# SCH_SIM808_ArduinoNano.net
KiCad netlist of a schematic drawn in Altium Designer
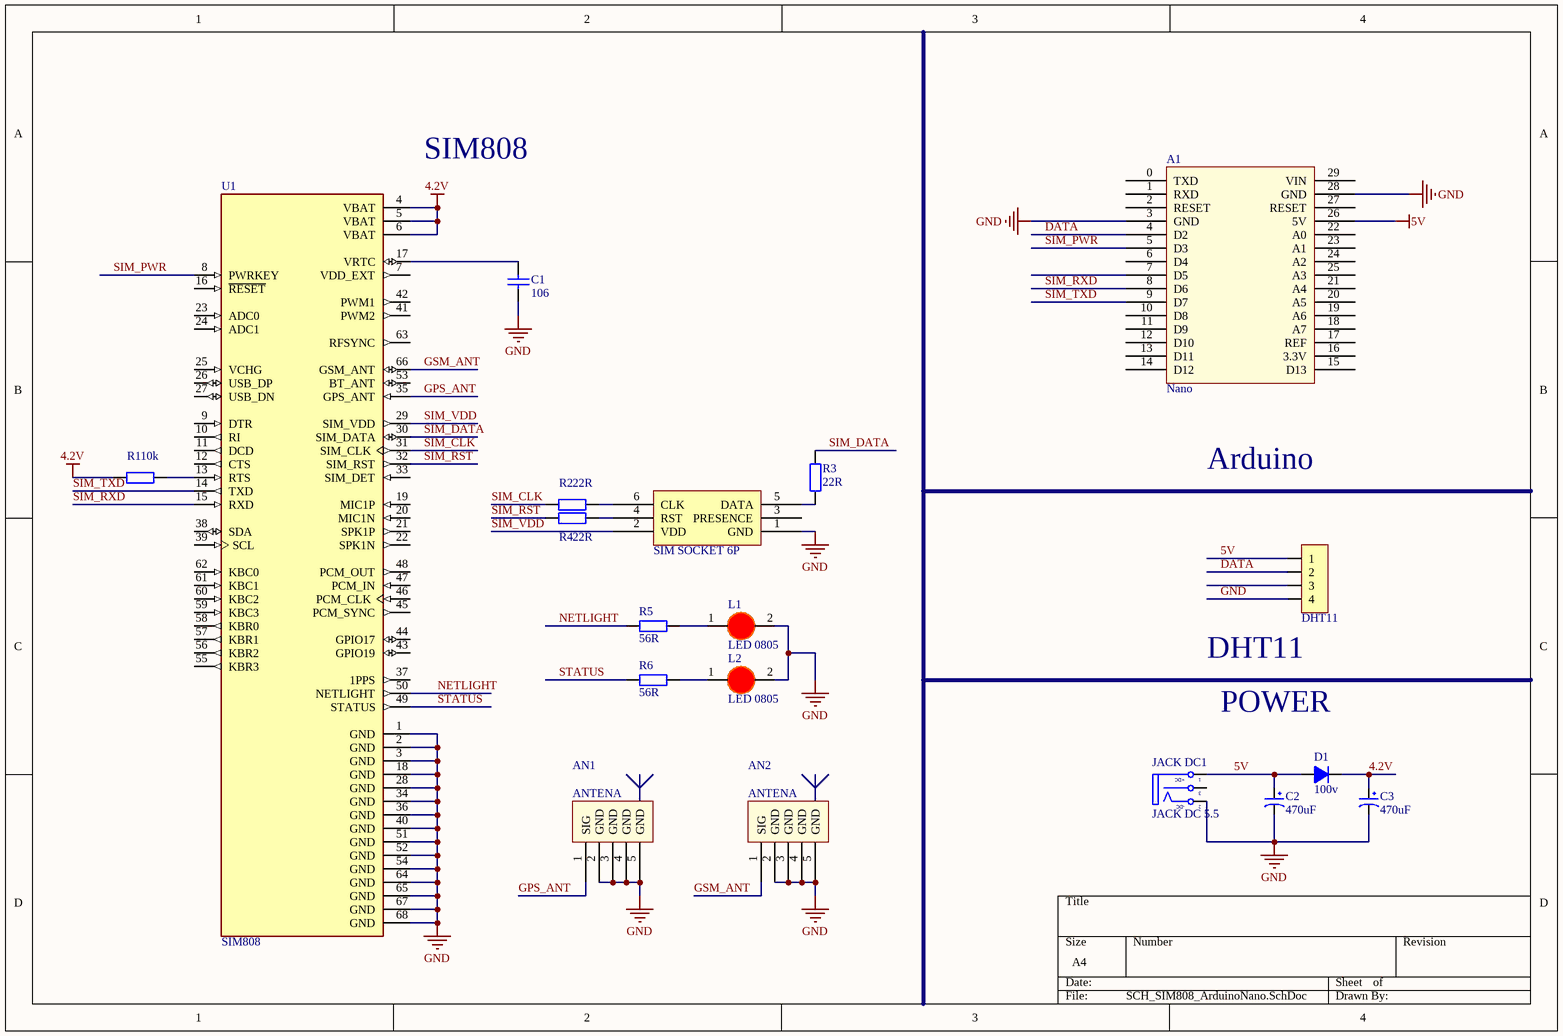
[diagram p0: SCH_SIM808_ArduinoNano.SchDoc]

(export (version "E")
  (design (tool "Eeschema 10.0.6"))
  (components
    (comp (ref "A1")
      (value "Nano")
      (footprint "Arduino nano")
      (libsource (lib "Altium_Lib_by_KhueNguyenCreator") (part "Arduino Nano"))
    )
    (comp (ref "AN1")
      (value "ANTENA")
      (footprint "DE ANTEN SMA CONG")
      (description "Generic Antenna")
      (libsource (lib "Altium_Lib_by_KhueNguyenCreator") (part "ANTEN SMA CONG"))
    )
    (comp (ref "AN2")
      (value "ANTENA")
      (footprint "DE ANTEN SMA CONG")
      (description "Generic Antenna")
      (libsource (lib "Altium_Lib_by_KhueNguyenCreator") (part "ANTEN SMA CONG"))
    )
    (comp (ref "C1")
      (value "106")
      (footprint "tu 0805")
      (description "Dán")
      (libsource (lib "Altium_Lib_by_KhueNguyenCreator") (part "Tu 0805 106 16V 10%"))
    )
    (comp (ref "C2")
      (value "470uF")
      (footprint "tu tantalum smd7343")
      (description "Dán")
      (libsource (lib "Altium_Lib_by_KhueNguyenCreator") (part "Tu tantalum 470uF 10V SMD7343"))
    )
    (comp (ref "C3")
      (value "470uF")
      (footprint "tu tantalum smd7343")
      (description "Dán")
      (libsource (lib "Altium_Lib_by_KhueNguyenCreator") (part "Tu tantalum 470uF 10V SMD7343"))
    )
    (comp (ref "D1")
      (value "100v")
      (footprint "DIODE 1A")
      (description "Cắm")
      (libsource (lib "Altium_Lib_by_KhueNguyenCreator") (part "Diode 1N4007"))
    )
    (comp (ref "JACK DC1")
      (value "JACK DC 5.5")
      (footprint "JACK DC 5.5")
      (libsource (lib "Altium_Lib_by_KhueNguyenCreator") (part "JACK DC 5.5"))
    )
    (comp (ref "JP1")
      (value "DHT11")
      (footprint "JP 1x4 DT")
      (description "Cắm")
      (libsource (lib "Altium_Lib_by_KhueNguyenCreator") (part "JP 1x4 2.54 Duc Thang"))
    )
    (comp (ref "L1")
      (value "LED 0805")
      (footprint "LED-0805-Red")
      (description "Dán")
      (libsource (lib "Altium_Lib_by_KhueNguyenCreator") (part "LED 0805 Do"))
    )
    (comp (ref "L2")
      (value "LED 0805")
      (footprint "LED-0805-Red")
      (description "Dán")
      (libsource (lib "Altium_Lib_by_KhueNguyenCreator") (part "LED 0805 Do"))
    )
    (comp (ref "R1")
      (value "10k")
      (footprint "tro smd 0805")
      (description "Dán")
      (libsource (lib "Altium_Lib_by_KhueNguyenCreator") (part "Tro 0805 5% 10k"))
    )
    (comp (ref "R2")
      (value "22R")
      (footprint "tro smd 0805")
      (description "Dán")
      (libsource (lib "Altium_Lib_by_KhueNguyenCreator") (part "Tro 0805 5% 22R"))
    )
    (comp (ref "R3")
      (value "22R")
      (footprint "tro smd 0805")
      (description "Dán")
      (libsource (lib "Altium_Lib_by_KhueNguyenCreator") (part "Tro 0805 5% 22R"))
    )
    (comp (ref "R4")
      (value "22R")
      (footprint "tro smd 0805")
      (description "Dán")
      (libsource (lib "Altium_Lib_by_KhueNguyenCreator") (part "Tro 0805 5% 22R"))
    )
    (comp (ref "R5")
      (value "56R")
      (footprint "tro smd 0805")
      (description "Dán")
      (libsource (lib "Altium_Lib_by_KhueNguyenCreator") (part "Tro 0805 5% 56R"))
    )
    (comp (ref "R6")
      (value "56R")
      (footprint "tro smd 0805")
      (description "Dán")
      (libsource (lib "Altium_Lib_by_KhueNguyenCreator") (part "Tro 0805 5% 56R"))
    )
    (comp (ref "SIM1")
      (value "SIM SOCKET 6P")
      (footprint "SIM SOCKET 6P")
      (libsource (lib "Altium_Lib_by_KhueNguyenCreator") (part "SIM SOCKET 6P"))
    )
    (comp (ref "U1")
      (value "SIM808")
      (footprint "SIM808")
      (description "SIM808 GPS, GPRS/GSM RF Arduino Platform Evaluation Expansion Board")
      (fields (field (name "MF") "Adafruit Industries"))
      (libsource (lib "Altium_Lib_by_KhueNguyenCreator") (part "SIM808"))
    )
  )
  (nets
    (net (code "1") (name "/DATA") (class "Default")
      (node (ref "A1") (pin "4") (pinfunction "D2_4") (pintype "passive"))
      (node (ref "JP1") (pin "2") (pinfunction "2_2") (pintype "passive"))
    )
    (net (code "2") (name "/GPS_ANT") (class "Default")
      (node (ref "AN1") (pin "1") (pinfunction "SIG_1") (pintype "passive"))
      (node (ref "U1") (pin "35") (pinfunction "GPS_ANT_35") (pintype "input"))
    )
    (net (code "3") (name "/GSM_ANT") (class "Default")
      (node (ref "AN2") (pin "1") (pinfunction "SIG_1") (pintype "passive"))
      (node (ref "U1") (pin "66") (pinfunction "GSM_ANT_66") (pintype "bidirectional"))
    )
    (net (code "4") (name "/NETLIGHT") (class "Default")
      (node (ref "R5") (pin "1") (pinfunction "1_1") (pintype "passive"))
      (node (ref "U1") (pin "50") (pinfunction "NETLIGHT_50") (pintype "output"))
    )
    (net (code "5") (name "/SIM_CLK") (class "Default")
      (node (ref "R2") (pin "1") (pinfunction "1_1") (pintype "passive"))
      (node (ref "U1") (pin "31") (pinfunction "SIM_CLK_31") (pintype "output"))
    )
    (net (code "6") (name "/SIM_DATA") (class "Default")
      (node (ref "R3") (pin "2") (pinfunction "2_2") (pintype "passive"))
      (node (ref "U1") (pin "30") (pinfunction "SIM_DATA_30") (pintype "bidirectional"))
    )
    (net (code "7") (name "/SIM_PWR") (class "Default")
      (node (ref "A1") (pin "5") (pinfunction "D3_5") (pintype "passive"))
      (node (ref "U1") (pin "8") (pinfunction "PWRKEY_8") (pintype "input"))
    )
    (net (code "8") (name "/SIM_RST") (class "Default")
      (node (ref "R4") (pin "1") (pinfunction "1_1") (pintype "passive"))
      (node (ref "U1") (pin "32") (pinfunction "SIM_RST_32") (pintype "output"))
    )
    (net (code "9") (name "/SIM_RXD") (class "Default")
      (node (ref "A1") (pin "8") (pinfunction "D6_8") (pintype "passive"))
      (node (ref "U1") (pin "15") (pinfunction "RXD_15") (pintype "input"))
    )
    (net (code "10") (name "/SIM_TXD") (class "Default")
      (node (ref "A1") (pin "9") (pinfunction "D7_9") (pintype "passive"))
      (node (ref "U1") (pin "14") (pinfunction "TXD_14") (pintype "output"))
    )
    (net (code "11") (name "/SIM_VDD") (class "Default")
      (node (ref "SIM1") (pin "2") (pinfunction "VDD_2") (pintype "passive"))
      (node (ref "U1") (pin "29") (pinfunction "SIM_VDD_29") (pintype "output"))
    )
    (net (code "12") (name "/STATUS") (class "Default")
      (node (ref "R6") (pin "1") (pinfunction "1_1") (pintype "passive"))
      (node (ref "U1") (pin "49") (pinfunction "STATUS_49") (pintype "output"))
    )
    (net (code "13") (name "4.2V") (class "Default")
      (node (ref "C3") (pin "1") (pinfunction "1_1") (pintype "passive"))
      (node (ref "D1") (pin "2") (pinfunction "K_2") (pintype "passive"))
      (node (ref "R1") (pin "1") (pinfunction "1_1") (pintype "passive"))
      (node (ref "U1") (pin "4") (pinfunction "VBAT_4") (pintype "power_in"))
      (node (ref "U1") (pin "5") (pinfunction "VBAT_5") (pintype "power_in"))
      (node (ref "U1") (pin "6") (pinfunction "VBAT_6") (pintype "power_in"))
    )
    (net (code "14") (name "5V") (class "Default")
      (node (ref "A1") (pin "26") (pinfunction "5V_26") (pintype "passive"))
      (node (ref "C2") (pin "1") (pinfunction "1_1") (pintype "passive"))
      (node (ref "D1") (pin "1") (pinfunction "A_1") (pintype "passive"))
      (node (ref "JACK DC1") (pin "1") (pinfunction "T_1") (pintype "passive"))
      (node (ref "JP1") (pin "1") (pinfunction "1_1") (pintype "passive"))
    )
    (net (code "15") (name "GND") (class "Default")
      (node (ref "A1") (pin "28") (pinfunction "GND_28") (pintype "passive"))
      (node (ref "A1") (pin "3") (pinfunction "GND_3") (pintype "passive"))
      (node (ref "AN1") (pin "2") (pinfunction "GND_2") (pintype "passive"))
      (node (ref "AN1") (pin "3") (pinfunction "GND_3") (pintype "passive"))
      (node (ref "AN1") (pin "4") (pinfunction "GND_4") (pintype "passive"))
      (node (ref "AN1") (pin "5") (pinfunction "GND_5") (pintype "passive"))
      (node (ref "AN2") (pin "2") (pinfunction "GND_2") (pintype "passive"))
      (node (ref "AN2") (pin "3") (pinfunction "GND_3") (pintype "passive"))
      (node (ref "AN2") (pin "4") (pinfunction "GND_4") (pintype "passive"))
      (node (ref "AN2") (pin "5") (pinfunction "GND_5") (pintype "passive"))
      (node (ref "C1") (pin "2") (pinfunction "2_2") (pintype "passive"))
      (node (ref "C2") (pin "2") (pinfunction "2_2") (pintype "passive"))
      (node (ref "C3") (pin "2") (pinfunction "2_2") (pintype "passive"))
      (node (ref "JACK DC1") (pin "2") (pinfunction "TN_2") (pintype "passive"))
      (node (ref "JP1") (pin "4") (pinfunction "4_4") (pintype "passive"))
      (node (ref "L1") (pin "2") (pinfunction "K_2") (pintype "passive"))
      (node (ref "L2") (pin "2") (pinfunction "K_2") (pintype "passive"))
      (node (ref "SIM1") (pin "1") (pinfunction "GND_1") (pintype "passive"))
      (node (ref "U1") (pin "1") (pinfunction "GND_1") (pintype "power_in"))
      (node (ref "U1") (pin "18") (pinfunction "GND_18") (pintype "power_in"))
      (node (ref "U1") (pin "2") (pinfunction "GND_2") (pintype "power_in"))
      (node (ref "U1") (pin "28") (pinfunction "GND_28") (pintype "power_in"))
      (node (ref "U1") (pin "3") (pinfunction "GND_3") (pintype "power_in"))
      (node (ref "U1") (pin "34") (pinfunction "GND_34") (pintype "power_in"))
      (node (ref "U1") (pin "36") (pinfunction "GND_36") (pintype "power_in"))
      (node (ref "U1") (pin "40") (pinfunction "GND_40") (pintype "power_in"))
      (node (ref "U1") (pin "51") (pinfunction "GND_51") (pintype "power_in"))
      (node (ref "U1") (pin "52") (pinfunction "GND_52") (pintype "power_in"))
      (node (ref "U1") (pin "54") (pinfunction "GND_54") (pintype "power_in"))
      (node (ref "U1") (pin "64") (pinfunction "GND_64") (pintype "power_in"))
      (node (ref "U1") (pin "65") (pinfunction "GND_65") (pintype "power_in"))
      (node (ref "U1") (pin "67") (pinfunction "GND_67") (pintype "power_in"))
      (node (ref "U1") (pin "68") (pinfunction "GND_68") (pintype "power_in"))
    )
    (net (code "16") (name "Net-(L1-A)") (class "Default")
      (node (ref "L1") (pin "1") (pinfunction "A_1") (pintype "passive"))
      (node (ref "R5") (pin "2") (pinfunction "2_2") (pintype "passive"))
    )
    (net (code "17") (name "Net-(L2-A)") (class "Default")
      (node (ref "L2") (pin "1") (pinfunction "A_1") (pintype "passive"))
      (node (ref "R6") (pin "2") (pinfunction "2_2") (pintype "passive"))
    )
    (net (code "18") (name "Net-(SIM1-CLK)") (class "Default")
      (node (ref "R2") (pin "2") (pinfunction "2_2") (pintype "passive"))
      (node (ref "SIM1") (pin "6") (pinfunction "CLK_6") (pintype "passive"))
    )
    (net (code "19") (name "Net-(SIM1-DATA)") (class "Default")
      (node (ref "R3") (pin "1") (pinfunction "1_1") (pintype "passive"))
      (node (ref "SIM1") (pin "5") (pinfunction "DATA_5") (pintype "passive"))
    )
    (net (code "20") (name "Net-(SIM1-RST)") (class "Default")
      (node (ref "R4") (pin "2") (pinfunction "2_2") (pintype "passive"))
      (node (ref "SIM1") (pin "4") (pinfunction "RST_4") (pintype "passive"))
    )
    (net (code "21") (name "Net-(U1-RTS)") (class "Default")
      (node (ref "R1") (pin "2") (pinfunction "2_2") (pintype "passive"))
      (node (ref "U1") (pin "13") (pinfunction "RTS_13") (pintype "input"))
    )
    (net (code "22") (name "Net-(U1-VRTC)") (class "Default")
      (node (ref "C1") (pin "1") (pinfunction "1_1") (pintype "passive"))
      (node (ref "U1") (pin "17") (pinfunction "VRTC_17") (pintype "bidirectional"))
    )
    (net (code "23") (name "unconnected-(A1-3.3V-Pad16)") (class "Default")
      (node (ref "A1") (pin "16") (pinfunction "3.3V_16") (pintype "passive"))
    )
    (net (code "24") (name "unconnected-(A1-A0-Pad22)") (class "Default")
      (node (ref "A1") (pin "22") (pinfunction "A0_22") (pintype "passive"))
    )
    (net (code "25") (name "unconnected-(A1-A1-Pad23)") (class "Default")
      (node (ref "A1") (pin "23") (pinfunction "A1_23") (pintype "passive"))
    )
    (net (code "26") (name "unconnected-(A1-A2-Pad24)") (class "Default")
      (node (ref "A1") (pin "24") (pinfunction "A2_24") (pintype "passive"))
    )
    (net (code "27") (name "unconnected-(A1-A3-Pad25)") (class "Default")
      (node (ref "A1") (pin "25") (pinfunction "A3_25") (pintype "passive"))
    )
    (net (code "28") (name "unconnected-(A1-A4-Pad21)") (class "Default")
      (node (ref "A1") (pin "21") (pinfunction "A4_21") (pintype "passive"))
    )
    (net (code "29") (name "unconnected-(A1-A5-Pad20)") (class "Default")
      (node (ref "A1") (pin "20") (pinfunction "A5_20") (pintype "passive"))
    )
    (net (code "30") (name "unconnected-(A1-A6-Pad19)") (class "Default")
      (node (ref "A1") (pin "19") (pinfunction "A6_19") (pintype "passive"))
    )
    (net (code "31") (name "unconnected-(A1-A7-Pad18)") (class "Default")
      (node (ref "A1") (pin "18") (pinfunction "A7_18") (pintype "passive"))
    )
    (net (code "32") (name "unconnected-(A1-D4-Pad6)") (class "Default")
      (node (ref "A1") (pin "6") (pinfunction "D4_6") (pintype "passive"))
    )
    (net (code "33") (name "unconnected-(A1-D5-Pad7)") (class "Default")
      (node (ref "A1") (pin "7") (pinfunction "D5_7") (pintype "passive"))
    )
    (net (code "34") (name "unconnected-(A1-D8-Pad10)") (class "Default")
      (node (ref "A1") (pin "10") (pinfunction "D8_10") (pintype "passive"))
    )
    (net (code "35") (name "unconnected-(A1-D9-Pad11)") (class "Default")
      (node (ref "A1") (pin "11") (pinfunction "D9_11") (pintype "passive"))
    )
    (net (code "36") (name "unconnected-(A1-D10-Pad12)") (class "Default")
      (node (ref "A1") (pin "12") (pinfunction "D10_12") (pintype "passive"))
    )
    (net (code "37") (name "unconnected-(A1-D11-Pad13)") (class "Default")
      (node (ref "A1") (pin "13") (pinfunction "D11_13") (pintype "passive"))
    )
    (net (code "38") (name "unconnected-(A1-D12-Pad14)") (class "Default")
      (node (ref "A1") (pin "14") (pinfunction "D12_14") (pintype "passive"))
    )
    (net (code "39") (name "unconnected-(A1-D13-Pad15)") (class "Default")
      (node (ref "A1") (pin "15") (pinfunction "D13_15") (pintype "passive"))
    )
    (net (code "40") (name "unconnected-(A1-REF-Pad17)") (class "Default")
      (node (ref "A1") (pin "17") (pinfunction "REF_17") (pintype "passive"))
    )
    (net (code "41") (name "unconnected-(A1-RESET-Pad2)") (class "Default")
      (node (ref "A1") (pin "2") (pinfunction "RESET_2") (pintype "passive"))
    )
    (net (code "42") (name "unconnected-(A1-RESET-Pad27)") (class "Default")
      (node (ref "A1") (pin "27") (pinfunction "RESET_27") (pintype "passive"))
    )
    (net (code "43") (name "unconnected-(A1-RXD-Pad1)") (class "Default")
      (node (ref "A1") (pin "1") (pinfunction "RXD_1") (pintype "passive"))
    )
    (net (code "44") (name "unconnected-(A1-TXD-Pad0)") (class "Default")
      (node (ref "A1") (pin "0") (pinfunction "TXD_0") (pintype "passive"))
    )
    (net (code "45") (name "unconnected-(A1-VIN-Pad29)") (class "Default")
      (node (ref "A1") (pin "29") (pinfunction "VIN_29") (pintype "passive"))
    )
    (net (code "46") (name "unconnected-(JACK DC1-S-Pad3)") (class "Default")
      (node (ref "JACK DC1") (pin "3") (pinfunction "S_3") (pintype "power_in"))
    )
    (net (code "47") (name "unconnected-(JP1-Pad3)") (class "Default")
      (node (ref "JP1") (pin "3") (pinfunction "3_3") (pintype "passive"))
    )
    (net (code "48") (name "unconnected-(SIM1-PRESENCE-Pad3)") (class "Default")
      (node (ref "SIM1") (pin "3") (pinfunction "PRESENCE_3") (pintype "passive"))
    )
    (net (code "49") (name "unconnected-(U1-1PPS-Pad37)") (class "Default")
      (node (ref "U1") (pin "37") (pinfunction "1PPS_37") (pintype "output"))
    )
    (net (code "50") (name "unconnected-(U1-ADC0-Pad23)") (class "Default")
      (node (ref "U1") (pin "23") (pinfunction "ADC0_23") (pintype "input"))
    )
    (net (code "51") (name "unconnected-(U1-ADC1-Pad24)") (class "Default")
      (node (ref "U1") (pin "24") (pinfunction "ADC1_24") (pintype "input"))
    )
    (net (code "52") (name "unconnected-(U1-BT_ANT-Pad53)") (class "Default")
      (node (ref "U1") (pin "53") (pinfunction "BT_ANT_53") (pintype "bidirectional"))
    )
    (net (code "53") (name "unconnected-(U1-CTS-Pad12)") (class "Default")
      (node (ref "U1") (pin "12") (pinfunction "CTS_12") (pintype "output"))
    )
    (net (code "54") (name "unconnected-(U1-DCD-Pad11)") (class "Default")
      (node (ref "U1") (pin "11") (pinfunction "DCD_11") (pintype "output"))
    )
    (net (code "55") (name "unconnected-(U1-DTR-Pad9)") (class "Default")
      (node (ref "U1") (pin "9") (pinfunction "DTR_9") (pintype "input"))
    )
    (net (code "56") (name "unconnected-(U1-GPIO17-Pad44)") (class "Default")
      (node (ref "U1") (pin "44") (pinfunction "GPIO17_44") (pintype "bidirectional"))
    )
    (net (code "57") (name "unconnected-(U1-GPIO19-Pad43)") (class "Default")
      (node (ref "U1") (pin "43") (pinfunction "GPIO19_43") (pintype "bidirectional"))
    )
    (net (code "58") (name "unconnected-(U1-KBC0-Pad62)") (class "Default")
      (node (ref "U1") (pin "62") (pinfunction "KBC0_62") (pintype "input"))
    )
    (net (code "59") (name "unconnected-(U1-KBC1-Pad61)") (class "Default")
      (node (ref "U1") (pin "61") (pinfunction "KBC1_61") (pintype "input"))
    )
    (net (code "60") (name "unconnected-(U1-KBC2-Pad60)") (class "Default")
      (node (ref "U1") (pin "60") (pinfunction "KBC2_60") (pintype "input"))
    )
    (net (code "61") (name "unconnected-(U1-KBC3-Pad59)") (class "Default")
      (node (ref "U1") (pin "59") (pinfunction "KBC3_59") (pintype "input"))
    )
    (net (code "62") (name "unconnected-(U1-KBR0-Pad58)") (class "Default")
      (node (ref "U1") (pin "58") (pinfunction "KBR0_58") (pintype "output"))
    )
    (net (code "63") (name "unconnected-(U1-KBR1-Pad57)") (class "Default")
      (node (ref "U1") (pin "57") (pinfunction "KBR1_57") (pintype "output"))
    )
    (net (code "64") (name "unconnected-(U1-KBR2-Pad56)") (class "Default")
      (node (ref "U1") (pin "56") (pinfunction "KBR2_56") (pintype "output"))
    )
    (net (code "65") (name "unconnected-(U1-KBR3-Pad55)") (class "Default")
      (node (ref "U1") (pin "55") (pinfunction "KBR3_55") (pintype "output"))
    )
    (net (code "66") (name "unconnected-(U1-MIC1N-Pad20)") (class "Default")
      (node (ref "U1") (pin "20") (pinfunction "MIC1N_20") (pintype "input"))
    )
    (net (code "67") (name "unconnected-(U1-MIC1P-Pad19)") (class "Default")
      (node (ref "U1") (pin "19") (pinfunction "MIC1P_19") (pintype "input"))
    )
    (net (code "68") (name "unconnected-(U1-PCM_CLK-Pad46)") (class "Default")
      (node (ref "U1") (pin "46") (pinfunction "PCM_CLK_46") (pintype "input"))
    )
    (net (code "69") (name "unconnected-(U1-PCM_IN-Pad47)") (class "Default")
      (node (ref "U1") (pin "47") (pinfunction "PCM_IN_47") (pintype "input"))
    )
    (net (code "70") (name "unconnected-(U1-PCM_OUT-Pad48)") (class "Default")
      (node (ref "U1") (pin "48") (pinfunction "PCM_OUT_48") (pintype "output"))
    )
    (net (code "71") (name "unconnected-(U1-PCM_SYNC-Pad45)") (class "Default")
      (node (ref "U1") (pin "45") (pinfunction "PCM_SYNC_45") (pintype "output"))
    )
    (net (code "72") (name "unconnected-(U1-PWM1-Pad42)") (class "Default")
      (node (ref "U1") (pin "42") (pinfunction "PWM1_42") (pintype "output"))
    )
    (net (code "73") (name "unconnected-(U1-PWM2-Pad41)") (class "Default")
      (node (ref "U1") (pin "41") (pinfunction "PWM2_41") (pintype "output"))
    )
    (net (code "74") (name "unconnected-(U1-RFSYNC-Pad63)") (class "Default")
      (node (ref "U1") (pin "63") (pinfunction "RFSYNC_63") (pintype "output"))
    )
    (net (code "75") (name "unconnected-(U1-RI-Pad10)") (class "Default")
      (node (ref "U1") (pin "10") (pinfunction "RI_10") (pintype "output"))
    )
    (net (code "76") (name "unconnected-(U1-SCL-Pad39)") (class "Default")
      (node (ref "U1") (pin "39") (pinfunction "SCL_39") (pintype "input"))
    )
    (net (code "77") (name "unconnected-(U1-SDA-Pad38)") (class "Default")
      (node (ref "U1") (pin "38") (pinfunction "SDA_38") (pintype "bidirectional"))
    )
    (net (code "78") (name "unconnected-(U1-SIM_DET-Pad33)") (class "Default")
      (node (ref "U1") (pin "33") (pinfunction "SIM_DET_33") (pintype "input"))
    )
    (net (code "79") (name "unconnected-(U1-SPK1N-Pad22)") (class "Default")
      (node (ref "U1") (pin "22") (pinfunction "SPK1N_22") (pintype "output"))
    )
    (net (code "80") (name "unconnected-(U1-SPK1P-Pad21)") (class "Default")
      (node (ref "U1") (pin "21") (pinfunction "SPK1P_21") (pintype "output"))
    )
    (net (code "81") (name "unconnected-(U1-USB_DN-Pad27)") (class "Default")
      (node (ref "U1") (pin "27") (pinfunction "USB_DN_27") (pintype "bidirectional"))
    )
    (net (code "82") (name "unconnected-(U1-USB_DP-Pad26)") (class "Default")
      (node (ref "U1") (pin "26") (pinfunction "USB_DP_26") (pintype "bidirectional"))
    )
    (net (code "83") (name "unconnected-(U1-VCHG-Pad25)") (class "Default")
      (node (ref "U1") (pin "25") (pinfunction "VCHG_25") (pintype "input"))
    )
    (net (code "84") (name "unconnected-(U1-VDD_EXT-Pad7)") (class "Default")
      (node (ref "U1") (pin "7") (pinfunction "VDD_EXT_7") (pintype "output"))
    )
    (net (code "85") (name "unconnected-(U1-~{RESET}-Pad16)") (class "Default")
      (node (ref "U1") (pin "16") (pinfunction "~{RESET}_16") (pintype "input"))
    )
  )
)
